# opencopcho.net
KiCad netlist of a schematic drawn in EAGLE
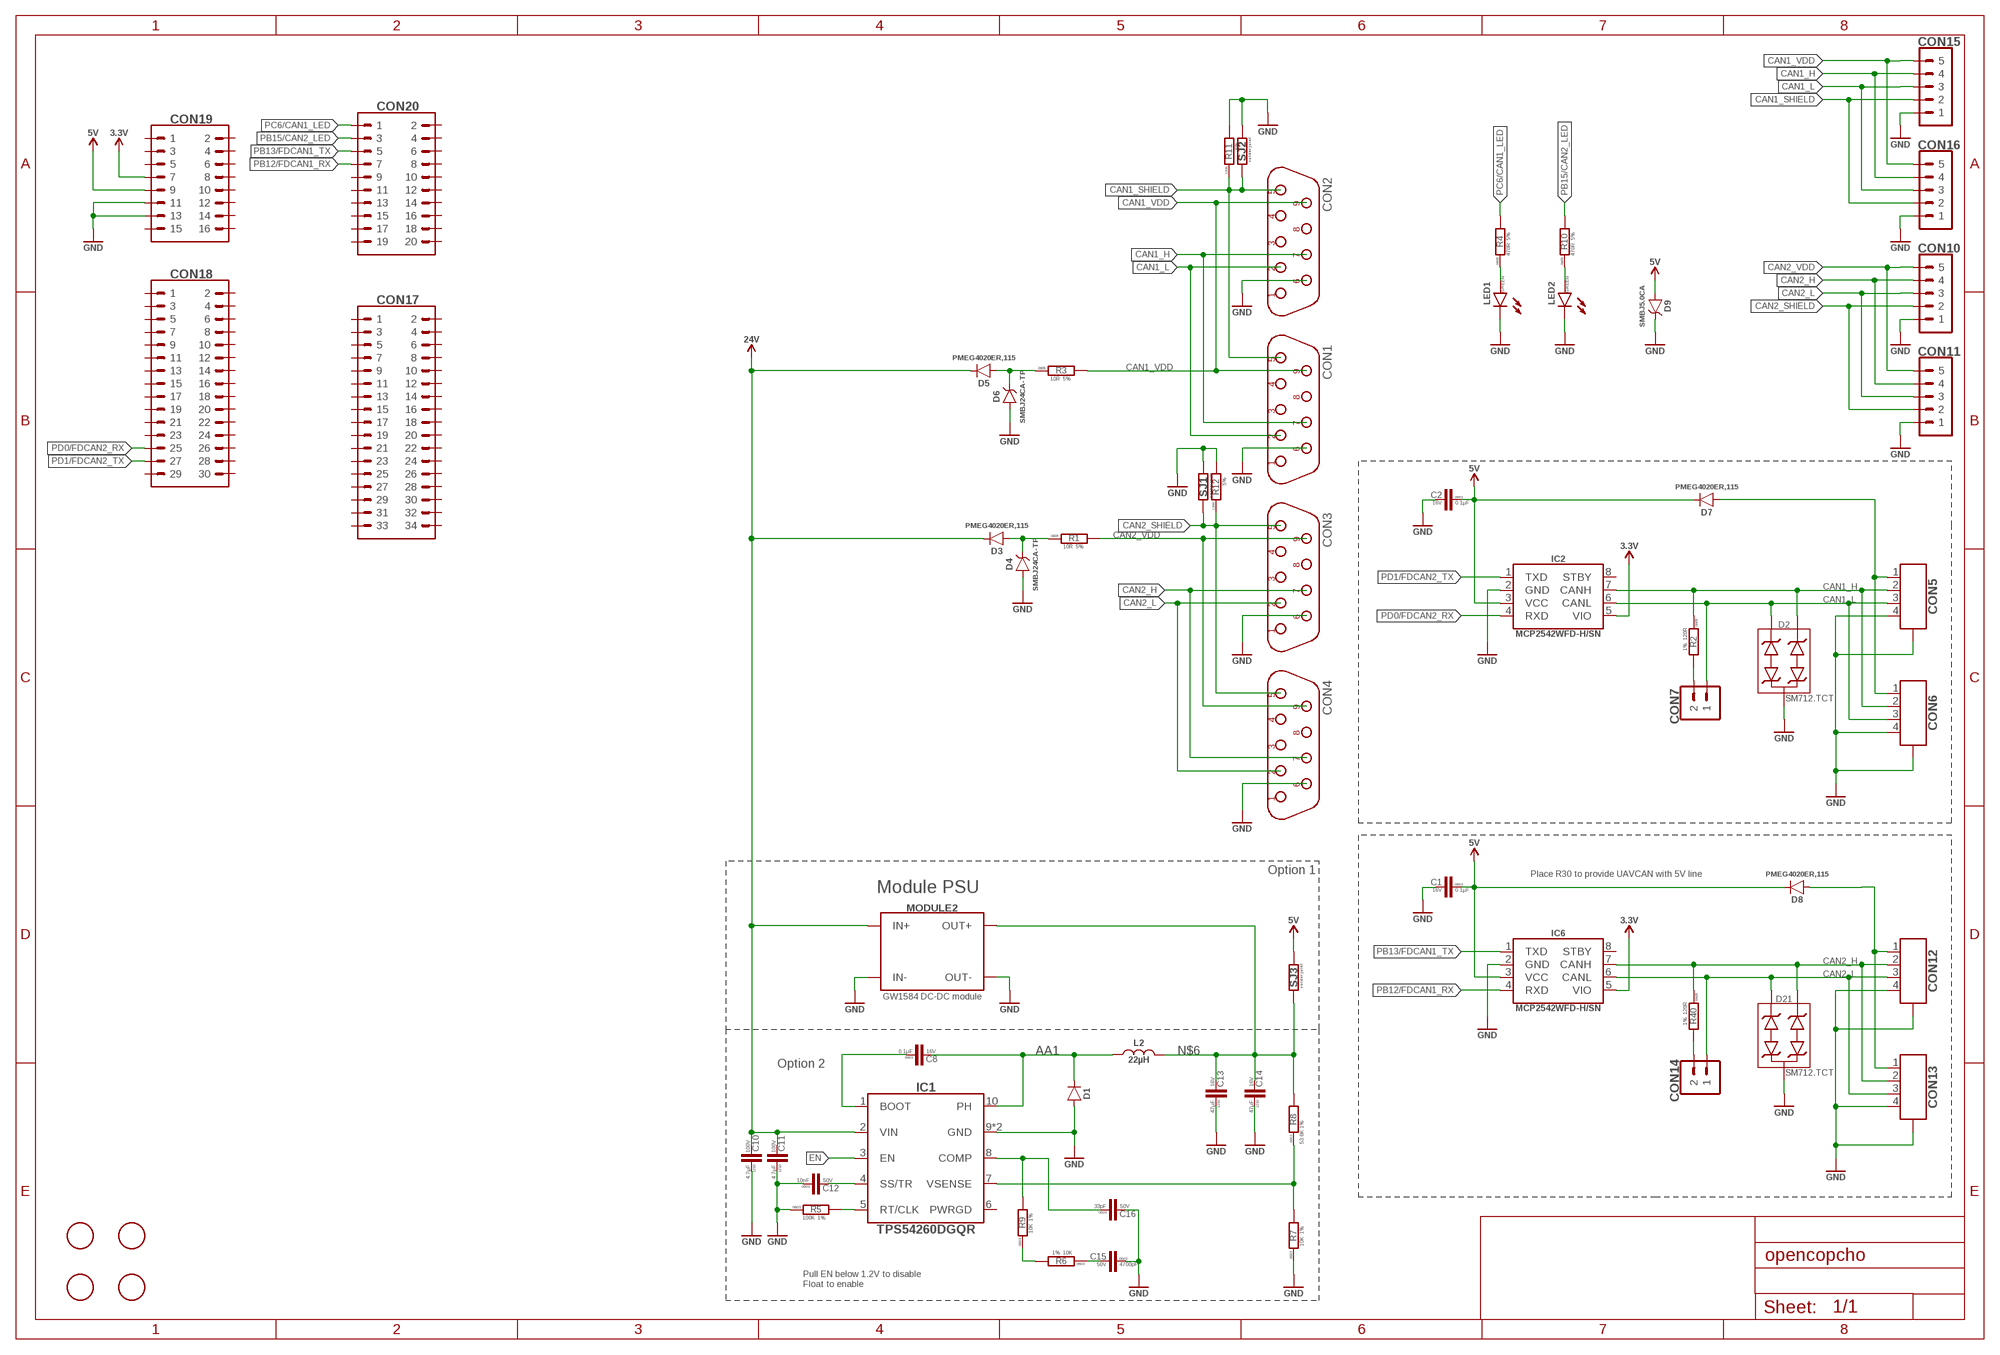
[diagram p0: schematic, sheet 1]

(export (version "E")
  (design (tool "Eeschema 10.0.6"))
  (components
    (comp (ref "C1")
      (value "0.1µF")
      (footprint "eagle-import:C0603")
      (fields
        (field (name "MANF") "Murata Electronics North America")
        (field (name "PACKAGE") "0603")
        (field (name "TOLERANCE") "+-10%")
        (field (name "VOLTAGE") "16V")
      )
      (libsource (lib "eagle-import") (part "0.1µF-0603-16V_10%_X7R"))
    )
    (comp (ref "C2")
      (value "0.1µF")
      (footprint "eagle-import:C0603")
      (fields
        (field (name "MANF") "Murata Electronics North America")
        (field (name "PACKAGE") "0603")
        (field (name "TOLERANCE") "+-10%")
        (field (name "VOLTAGE") "16V")
      )
      (libsource (lib "eagle-import") (part "0.1µF-0603-16V_10%_X7R"))
    )
    (comp (ref "C8")
      (value "0.1µF")
      (footprint "eagle-import:C0603")
      (fields
        (field (name "MANF") "Murata Electronics North America")
        (field (name "PACKAGE") "0603")
        (field (name "TOLERANCE") "+-10%")
        (field (name "VOLTAGE") "16V")
      )
      (libsource (lib "eagle-import") (part "0.1µF-0603-16V_10%_X7R"))
    )
    (comp (ref "C10")
      (value "4.7µF")
      (footprint "eagle-import:C1210")
      (fields
        (field (name "MANF") "TDK Corporation")
        (field (name "PACKAGE") "1210")
        (field (name "TOLERANCE") "+-20%")
        (field (name "VOLTAGE") "100V")
      )
      (libsource (lib "eagle-import") (part "4.7µF-1210-100V_20%_X7S"))
    )
    (comp (ref "C11")
      (value "4.7µF")
      (footprint "eagle-import:C1210")
      (fields
        (field (name "MANF") "TDK Corporation")
        (field (name "PACKAGE") "1210")
        (field (name "TOLERANCE") "+-20%")
        (field (name "VOLTAGE") "100V")
      )
      (libsource (lib "eagle-import") (part "4.7µF-1210-100V_20%_X7S"))
    )
    (comp (ref "C12")
      (value "10nF")
      (footprint "eagle-import:C0603")
      (fields
        (field (name "MANF") "YAGEO")
        (field (name "PACKAGE") "0603")
        (field (name "TOLERANCE") "+-10%")
        (field (name "VOLTAGE") "50V")
      )
      (libsource (lib "eagle-import") (part "10NF-0603-50V_10%_X7R"))
    )
    (comp (ref "C13")
      (value "47µF")
      (footprint "eagle-import:C1210")
      (fields
        (field (name "MANF") "Murata Electronics North America")
        (field (name "PACKAGE") "1210")
        (field (name "TOLERANCE") "+-20%")
        (field (name "VOLTAGE") "16V")
      )
      (libsource (lib "eagle-import") (part "47µF-1210-16V_20%_X5R"))
    )
    (comp (ref "C14")
      (value "47µF")
      (footprint "eagle-import:C1210")
      (fields
        (field (name "MANF") "Murata Electronics North America")
        (field (name "PACKAGE") "1210")
        (field (name "TOLERANCE") "+-20%")
        (field (name "VOLTAGE") "16V")
      )
      (libsource (lib "eagle-import") (part "47µF-1210-16V_20%_X5R"))
    )
    (comp (ref "C15")
      (value "4700pF")
      (footprint "eagle-import:C0603")
      (fields
        (field (name "MANF") "Murata Electronics North America")
        (field (name "PACKAGE") "0603")
        (field (name "TOLERANCE") "+-10%")
        (field (name "VOLTAGE") "50V")
      )
      (libsource (lib "eagle-import") (part "4700PF-0603-50V_10%_X7R"))
    )
    (comp (ref "C16")
      (value "33pF")
      (footprint "eagle-import:C0603")
      (fields
        (field (name "MANF") "Murata Electronics North America")
        (field (name "PACKAGE") "0603")
        (field (name "TOLERANCE") "+-5%")
        (field (name "VOLTAGE") "50V")
      )
      (libsource (lib "eagle-import") (part "33PF-0603-50V_5%_NP0"))
    )
    (comp (ref "CON1")
      (value "DB9-M")
      (footprint "eagle-import:D-09M")
      (fields (field (name "MANF") "Assmann WSW Components"))
      (libsource (lib "eagle-import") (part "DB9-M"))
    )
    (comp (ref "CON2")
      (value "DB9-M")
      (footprint "eagle-import:D-09M")
      (fields (field (name "MANF") "Assmann WSW Components"))
      (libsource (lib "eagle-import") (part "DB9-M"))
    )
    (comp (ref "CON3")
      (value "DB9-M")
      (footprint "eagle-import:D-09M")
      (fields (field (name "MANF") "Assmann WSW Components"))
      (libsource (lib "eagle-import") (part "DB9-M"))
    )
    (comp (ref "CON4")
      (value "DB9-M")
      (footprint "eagle-import:D-09M")
      (fields (field (name "MANF") "Assmann WSW Components"))
      (libsource (lib "eagle-import") (part "DB9-M"))
    )
    (comp (ref "CON5")
      (value "CON-4P-JST_GH-RA")
      (footprint "eagle-import:JST_GH-4P-RA")
      (fields (field (name "MANF") "JST Sales America Inc"))
      (libsource (lib "eagle-import") (part "CON-4P-RA-JST_GH"))
    )
    (comp (ref "CON6")
      (value "CON-4P-JST_GH-RA")
      (footprint "eagle-import:JST_GH-4P-RA")
      (fields (field (name "MANF") "JST Sales America Inc"))
      (libsource (lib "eagle-import") (part "CON-4P-RA-JST_GH"))
    )
    (comp (ref "CON7")
      (value "PINHEAD_1X02-2.54")
      (footprint "eagle-import:1X02-PTH-2.54")
      (libsource (lib "eagle-import") (part "PINHEAD_1X02-2.54"))
    )
    (comp (ref "CON10")
      (value "PINHEAD_1X05-2.54-KEY")
      (footprint "eagle-import:1X05-PTH-2.54-KEY")
      (fields (field (name "MANF") "Sullins Connector Solutions"))
      (libsource (lib "eagle-import") (part "PINHEAD_1X05-2.54-KEY"))
    )
    (comp (ref "CON11")
      (value "PINHEAD_1X05-2.54-KEY")
      (footprint "eagle-import:1X05-PTH-2.54-KEY")
      (fields (field (name "MANF") "Sullins Connector Solutions"))
      (libsource (lib "eagle-import") (part "PINHEAD_1X05-2.54-KEY"))
    )
    (comp (ref "CON12")
      (value "CON-4P-JST_GH-RA")
      (footprint "eagle-import:JST_GH-4P-RA")
      (fields (field (name "MANF") "JST Sales America Inc"))
      (libsource (lib "eagle-import") (part "CON-4P-RA-JST_GH"))
    )
    (comp (ref "CON13")
      (value "CON-4P-JST_GH-RA")
      (footprint "eagle-import:JST_GH-4P-RA")
      (fields (field (name "MANF") "JST Sales America Inc"))
      (libsource (lib "eagle-import") (part "CON-4P-RA-JST_GH"))
    )
    (comp (ref "CON14")
      (value "PINHEAD_1X02-2.54")
      (footprint "eagle-import:1X02-PTH-2.54")
      (libsource (lib "eagle-import") (part "PINHEAD_1X02-2.54"))
    )
    (comp (ref "CON15")
      (value "PINHEAD_1X05-2.54-KEY")
      (footprint "eagle-import:1X05-PTH-2.54-KEY")
      (fields (field (name "MANF") "Sullins Connector Solutions"))
      (libsource (lib "eagle-import") (part "PINHEAD_1X05-2.54-KEY"))
    )
    (comp (ref "CON16")
      (value "PINHEAD_1X05-2.54-KEY")
      (footprint "eagle-import:1X05-PTH-2.54-KEY")
      (fields (field (name "MANF") "Sullins Connector Solutions"))
      (libsource (lib "eagle-import") (part "PINHEAD_1X05-2.54-KEY"))
    )
    (comp (ref "CON17")
      (value "PINHEAD_2X17-TH-FEMALE-LONG")
      (footprint "eagle-import:2X17-PTH-2.54-FEMALE-LONG_PINS")
      (fields (field (name "MANF") "Samtec Inc"))
      (libsource (lib "eagle-import") (part "PINHEAD_2X17-TH-FEMALE-LONG"))
    )
    (comp (ref "CON18")
      (value "PINHEAD_2X15-2.54-FEMALE-LONG")
      (footprint "eagle-import:2X15-PTH-2.54-FEMALE-LONG-PINS")
      (libsource (lib "eagle-import") (part "PINHEAD_2X15-2.54-FEMALE-LONG"))
    )
    (comp (ref "CON19")
      (value "PINHEAD_2X08-TH-FEMALE-LONG")
      (footprint "eagle-import:2X08-PTH-2.54-FEMALE-LONG-PINS")
      (fields (field (name "MANF") "Samtec Inc"))
      (libsource (lib "eagle-import") (part "PINHEAD_2X08-TH-FEMALE-LONG"))
    )
    (comp (ref "CON20")
      (value "PINHEAD_2X10-2.54-TH-FEMALE-LONG")
      (footprint "eagle-import:2X10-PTH-2.54-FEMALE-LONG-PINS")
      (fields (field (name "MANF") "Samtec Inc"))
      (libsource (lib "eagle-import") (part "PINHEAD_2X10-2.54-TH-FEMALE-LONG"))
    )
    (comp (ref "D1")
      (value "B360B")
      (footprint "eagle-import:DO-214AA(SMB)")
      (fields
        (field (name "MANF") "Diodes Incorporated")
        (field (name "DIGIKEY#") "B360B-FDICT-ND")
        (field (name "MANF_1") "Diodes Incorporated")
        (field (name "MANF#") "B360B-13-F")
      )
      (libsource (lib "eagle-import") (part "B360B"))
    )
    (comp (ref "D2")
      (value "SM712")
      (footprint "eagle-import:SOT23B-3")
      (fields (field (name "MANF#") "SM712.TCT") (field (name "MANF") "Semtech Corporation"))
      (libsource (lib "eagle-import") (part "SM712"))
    )
    (comp (ref "D3")
      (value "PMEG4020")
      (footprint "eagle-import:SOD123W")
      (fields
        (field (name "MANF#") "PMEG4020ER,115")
        (field (name "MANF") "NXP Semiconductors")
        (field (name "VOLTAGE") "40V")
      )
      (libsource (lib "eagle-import") (part "PMEG4020"))
    )
    (comp (ref "D4")
      (value "SMBJ24CA-SMB")
      (footprint "eagle-import:DO-214AA(SMB)")
      (fields (field (name "MANF#") "SMBJ24CA-TP") (field (name "MANF") "Micro Commercial Co"))
      (libsource (lib "eagle-import") (part "SMBJ24CA-SMB"))
    )
    (comp (ref "D5")
      (value "PMEG4020")
      (footprint "eagle-import:SOD123W")
      (fields
        (field (name "MANF#") "PMEG4020ER,115")
        (field (name "MANF") "NXP Semiconductors")
        (field (name "VOLTAGE") "40V")
      )
      (libsource (lib "eagle-import") (part "PMEG4020"))
    )
    (comp (ref "D6")
      (value "SMBJ24CA-SMB")
      (footprint "eagle-import:DO-214AA(SMB)")
      (fields (field (name "MANF#") "SMBJ24CA-TP") (field (name "MANF") "Micro Commercial Co"))
      (libsource (lib "eagle-import") (part "SMBJ24CA-SMB"))
    )
    (comp (ref "D7")
      (value "PMEG4020")
      (footprint "eagle-import:SOD123W")
      (fields
        (field (name "MANF#") "PMEG4020ER,115")
        (field (name "MANF") "NXP Semiconductors")
        (field (name "VOLTAGE") "40V")
      )
      (libsource (lib "eagle-import") (part "PMEG4020"))
    )
    (comp (ref "D8")
      (value "PMEG4020")
      (footprint "eagle-import:SOD123W")
      (fields
        (field (name "MANF#") "PMEG4020ER,115")
        (field (name "MANF") "NXP Semiconductors")
        (field (name "VOLTAGE") "40V")
      )
      (libsource (lib "eagle-import") (part "PMEG4020"))
    )
    (comp (ref "D9")
      (value "SMBJ5.0CA-SMB")
      (footprint "eagle-import:DO-214AA(SMB)")
      (fields (field (name "MANF#") "SMBJ5.0CA") (field (name "MANF") "Bourns Inc"))
      (libsource (lib "eagle-import") (part "SMBJ5.0CA-SMB"))
    )
    (comp (ref "D21")
      (value "SM712")
      (footprint "eagle-import:SOT23B-3")
      (fields (field (name "MANF#") "SM712.TCT") (field (name "MANF") "Semtech Corporation"))
      (libsource (lib "eagle-import") (part "SM712"))
    )
    (comp (ref "IC1")
      (value "TPS54260")
      (footprint "eagle-import:MSOP10")
      (fields (field (name "MANF#") "TPS54260DGQR") (field (name "MANF") "Texas Instruments"))
      (libsource (lib "eagle-import") (part "TPS54260"))
    )
    (comp (ref "IC2")
      (value "MCP2542WFD")
      (footprint "eagle-import:SOIC8-3.9")
      (fields (field (name "MANF#") "MCP2542WFD-H/SN") (field (name "MANF") "Microchip Technology"))
      (libsource (lib "eagle-import") (part "MCP2542WFD"))
    )
    (comp (ref "IC6")
      (value "MCP2542WFD")
      (footprint "eagle-import:SOIC8-3.9")
      (fields (field (name "MANF#") "MCP2542WFD-H/SN") (field (name "MANF") "Microchip Technology"))
      (libsource (lib "eagle-import") (part "MCP2542WFD"))
    )
    (comp (ref "L2")
      (value "22µH")
      (footprint "eagle-import:SRP6540")
      (fields
        (field (name "MANF") "Bourns Inc")
        (field (name "DIGIKEY#") "SRP6540-4R7MCT-ND")
        (field (name "MANF_1") "Bourns Inc")
        (field (name "MANF#") "SRP6540-4R7M")
      )
      (libsource (lib "eagle-import") (part "22µH-SRP6540-22U"))
    )
    (comp (ref "LED1")
      (value "LED-0805")
      (footprint "eagle-import:LED0805")
      (fields (field (name "COLOR") "GREEN"))
      (libsource (lib "eagle-import") (part "LED-0805"))
    )
    (comp (ref "LED2")
      (value "LED-0805")
      (footprint "eagle-import:LED0805")
      (fields (field (name "COLOR") "GREEN"))
      (libsource (lib "eagle-import") (part "LED-0805"))
    )
    (comp (ref "MODULE2")
      (value "GW1584_MODULE")
      (footprint "eagle-import:GW1584_MODULE")
      (libsource (lib "eagle-import") (part "GW1584_MODULE"))
    )
    (comp (ref "R1")
      (value "10R")
      (footprint "eagle-import:R0805")
      (fields (field (name "PACKAGE") "0805") (field (name "TOLERANCE") "5%"))
      (libsource (lib "eagle-import") (part "R-0805-5%"))
    )
    (comp (ref "R2")
      (value "120R")
      (footprint "eagle-import:R0805")
      (fields (field (name "PACKAGE") "0805") (field (name "TOLERANCE") "1%"))
      (libsource (lib "eagle-import") (part "R-0805-1%"))
    )
    (comp (ref "R3")
      (value "10R")
      (footprint "eagle-import:R0805")
      (fields (field (name "PACKAGE") "0805") (field (name "TOLERANCE") "5%"))
      (libsource (lib "eagle-import") (part "R-0805-5%"))
    )
    (comp (ref "R4")
      (value "470R")
      (footprint "eagle-import:R0805")
      (fields (field (name "PACKAGE") "0805") (field (name "TOLERANCE") "5%"))
      (libsource (lib "eagle-import") (part "R-0805-5%"))
    )
    (comp (ref "R5")
      (value "100K")
      (footprint "eagle-import:R0603")
      (fields (field (name "MANF") "Yageo") (field (name "PACKAGE") "0603") (field (name "TOLERANCE") "1%"))
      (libsource (lib "eagle-import") (part "100K-0603-1%"))
    )
    (comp (ref "R6")
      (value "10K")
      (footprint "eagle-import:R0603")
      (fields (field (name "MANF") "Yageo") (field (name "PACKAGE") "0603") (field (name "TOLERANCE") "1%"))
      (libsource (lib "eagle-import") (part "10K-0603-1%"))
    )
    (comp (ref "R7")
      (value "10K")
      (footprint "eagle-import:R0603")
      (fields (field (name "MANF") "Yageo") (field (name "PACKAGE") "0603") (field (name "TOLERANCE") "1%"))
      (libsource (lib "eagle-import") (part "10K-0603-1%"))
    )
    (comp (ref "R8")
      (value "53.6K 1%")
      (footprint "eagle-import:R0603")
      (fields (field (name "PACKAGE") "0603") (field (name "TOLERANCE") "1%") (field (name "MANF") "Yageo"))
      (libsource (lib "eagle-import") (part "R-0603-1%"))
    )
    (comp (ref "R9")
      (value "10K")
      (footprint "eagle-import:R0603")
      (fields (field (name "MANF") "Yageo") (field (name "PACKAGE") "0603") (field (name "TOLERANCE") "1%"))
      (libsource (lib "eagle-import") (part "10K-0603-1%"))
    )
    (comp (ref "R10")
      (value "470R")
      (footprint "eagle-import:R0805")
      (fields (field (name "PACKAGE") "0805") (field (name "TOLERANCE") "5%"))
      (libsource (lib "eagle-import") (part "R-0805-5%"))
    )
    (comp (ref "R11")
      (value "R-5%-1206")
      (footprint "eagle-import:R1206")
      (fields (field (name "PACKAGE") "1206") (field (name "TOLERANCE") "5%"))
      (libsource (lib "eagle-import") (part "R-1206-5%"))
    )
    (comp (ref "R12")
      (value "R-5%-1206")
      (footprint "eagle-import:R1206")
      (fields (field (name "PACKAGE") "1206") (field (name "TOLERANCE") "5%"))
      (libsource (lib "eagle-import") (part "R-1206-5%"))
    )
    (comp (ref "R40")
      (value "120R")
      (footprint "eagle-import:R0805")
      (fields (field (name "PACKAGE") "0805") (field (name "TOLERANCE") "1%"))
      (libsource (lib "eagle-import") (part "R-0805-1%"))
    )
    (comp (ref "SJ1")
      (value "SOLDER_JOINT")
      (footprint "eagle-import:RES_0")
      (libsource (lib "eagle-import") (part "SOLDER_JOINT"))
    )
    (comp (ref "SJ2")
      (value "SOLDER_JOINT")
      (footprint "eagle-import:RES_0")
      (libsource (lib "eagle-import") (part "SOLDER_JOINT"))
    )
    (comp (ref "SJ3")
      (value "SOLDER_JOINT")
      (footprint "eagle-import:RES_0")
      (libsource (lib "eagle-import") (part "SOLDER_JOINT"))
    )
    (comp (ref "U$5")
      (value "FIDUCIALMOUNT")
      (footprint "eagle-import:FIDUCIA-MOUNT")
      (libsource (lib "eagle-import") (part "FIDUCIALMOUNT"))
    )
    (comp (ref "U$6")
      (value "FIDUCIALMOUNT")
      (footprint "eagle-import:FIDUCIA-MOUNT")
      (libsource (lib "eagle-import") (part "FIDUCIALMOUNT"))
    )
    (comp (ref "U$7")
      (value "FIDUCIALMOUNT")
      (footprint "eagle-import:FIDUCIA-MOUNT")
      (libsource (lib "eagle-import") (part "FIDUCIALMOUNT"))
    )
    (comp (ref "U$11")
      (value "FIDUCIALMOUNT")
      (footprint "eagle-import:FIDUCIA-MOUNT")
      (libsource (lib "eagle-import") (part "FIDUCIALMOUNT"))
    )
  )
  (nets
    (net (code "1") (name "/AA1") (class "Default")
      (node (ref "C8") (pin "P$2") (pinfunction "2_P$2") (pintype "passive"))
      (node (ref "D1") (pin "C") (pinfunction "C_C") (pintype "passive"))
      (node (ref "IC1") (pin "10") (pinfunction "PH_10") (pintype "bidirectional"))
      (node (ref "L2") (pin "1") (pinfunction "P$1_1") (pintype "bidirectional"))
    )
    (net (code "2") (name "/N$6") (class "Default")
      (node (ref "C13") (pin "2") (pinfunction "2_2") (pintype "passive"))
      (node (ref "C14") (pin "2") (pinfunction "2_2") (pintype "passive"))
      (node (ref "L2") (pin "2") (pinfunction "P$2_2") (pintype "bidirectional"))
      (node (ref "MODULE2") (pin "OUT+@1") (pinfunction "OUT+_OUT+@1") (pintype "bidirectional"))
      (node (ref "MODULE2") (pin "OUT+@2") (pinfunction "OUT+_OUT+@2") (pintype "bidirectional"))
      (node (ref "R8") (pin "2") (pinfunction "2_2") (pintype "passive"))
      (node (ref "SJ3") (pin "1") (pinfunction "1_1") (pintype "passive"))
    )
    (net (code "3") (name "3.3V") (class "Default")
      (node (ref "CON19") (pin "7") (pinfunction "7_7") (pintype "passive"))
      (node (ref "IC2") (pin "5") (pinfunction "VIO_5") (pintype "bidirectional"))
      (node (ref "IC6") (pin "5") (pinfunction "VIO_5") (pintype "bidirectional"))
    )
    (net (code "4") (name "5V") (class "Default")
      (node (ref "C1") (pin "P$1") (pinfunction "1_P$1") (pintype "passive"))
      (node (ref "C2") (pin "P$1") (pinfunction "1_P$1") (pintype "passive"))
      (node (ref "CON19") (pin "9") (pinfunction "9_9") (pintype "passive"))
      (node (ref "D7") (pin "C") (pinfunction "C_C") (pintype "passive"))
      (node (ref "D8") (pin "C") (pinfunction "C_C") (pintype "passive"))
      (node (ref "D9") (pin "A") (pinfunction "A_A") (pintype "bidirectional"))
      (node (ref "IC2") (pin "3") (pinfunction "VCC_3") (pintype "bidirectional"))
      (node (ref "IC6") (pin "3") (pinfunction "VCC_3") (pintype "bidirectional"))
      (node (ref "SJ3") (pin "2") (pinfunction "2_2") (pintype "passive"))
    )
    (net (code "5") (name "24V") (class "Default")
      (node (ref "C10") (pin "2") (pinfunction "2_2") (pintype "passive"))
      (node (ref "C11") (pin "2") (pinfunction "2_2") (pintype "passive"))
      (node (ref "D3") (pin "C") (pinfunction "C_C") (pintype "passive"))
      (node (ref "D5") (pin "C") (pinfunction "C_C") (pintype "passive"))
      (node (ref "IC1") (pin "2") (pinfunction "VIN_2") (pintype "bidirectional"))
      (node (ref "MODULE2") (pin "IN+@1") (pinfunction "IN+_IN+@1") (pintype "bidirectional"))
      (node (ref "MODULE2") (pin "IN+@2") (pinfunction "IN+_IN+@2") (pintype "bidirectional"))
    )
    (net (code "6") (name "CAN1_H") (class "Default")
      (node (ref "CON1") (pin "7") (pinfunction "7_7") (pintype "passive"))
      (node (ref "CON15") (pin "4") (pinfunction "4_4") (pintype "passive"))
      (node (ref "CON16") (pin "4") (pinfunction "4_4") (pintype "passive"))
      (node (ref "CON2") (pin "7") (pinfunction "7_7") (pintype "passive"))
      (node (ref "CON5") (pin "2") (pinfunction "2_2") (pintype "bidirectional"))
      (node (ref "CON6") (pin "2") (pinfunction "2_2") (pintype "bidirectional"))
      (node (ref "D2") (pin "1") (pinfunction "C3_1") (pintype "bidirectional"))
      (node (ref "IC2") (pin "7") (pinfunction "CANH_7") (pintype "bidirectional"))
      (node (ref "R2") (pin "1") (pinfunction "1_1") (pintype "passive"))
    )
    (net (code "7") (name "CAN1_L") (class "Default")
      (node (ref "CON1") (pin "2") (pinfunction "2_2") (pintype "passive"))
      (node (ref "CON15") (pin "3") (pinfunction "3_3") (pintype "passive"))
      (node (ref "CON16") (pin "3") (pinfunction "3_3") (pintype "passive"))
      (node (ref "CON2") (pin "2") (pinfunction "2_2") (pintype "passive"))
      (node (ref "CON5") (pin "3") (pinfunction "3_3") (pintype "bidirectional"))
      (node (ref "CON6") (pin "3") (pinfunction "3_3") (pintype "bidirectional"))
      (node (ref "CON7") (pin "1") (pinfunction "1_1") (pintype "passive"))
      (node (ref "D2") (pin "2") (pinfunction "C2_2") (pintype "bidirectional"))
      (node (ref "IC2") (pin "6") (pinfunction "CANL_6") (pintype "bidirectional"))
    )
    (net (code "8") (name "CAN1_SHIELD") (class "Default")
      (node (ref "CON1") (pin "5") (pinfunction "5_5") (pintype "passive"))
      (node (ref "CON15") (pin "2") (pinfunction "2_2") (pintype "passive"))
      (node (ref "CON16") (pin "2") (pinfunction "2_2") (pintype "passive"))
      (node (ref "CON2") (pin "5") (pinfunction "5_5") (pintype "passive"))
      (node (ref "R11") (pin "P$1") (pinfunction "1_P$1") (pintype "passive"))
      (node (ref "SJ2") (pin "1") (pinfunction "1_1") (pintype "passive"))
    )
    (net (code "9") (name "CAN1_VDD") (class "Default")
      (node (ref "CON1") (pin "9") (pinfunction "9_9") (pintype "passive"))
      (node (ref "CON15") (pin "5") (pinfunction "5_5") (pintype "passive"))
      (node (ref "CON16") (pin "5") (pinfunction "5_5") (pintype "passive"))
      (node (ref "CON2") (pin "9") (pinfunction "9_9") (pintype "passive"))
      (node (ref "R3") (pin "2") (pinfunction "2_2") (pintype "passive"))
    )
    (net (code "10") (name "CAN2_H") (class "Default")
      (node (ref "CON10") (pin "4") (pinfunction "4_4") (pintype "passive"))
      (node (ref "CON11") (pin "4") (pinfunction "4_4") (pintype "passive"))
      (node (ref "CON12") (pin "2") (pinfunction "2_2") (pintype "bidirectional"))
      (node (ref "CON13") (pin "2") (pinfunction "2_2") (pintype "bidirectional"))
      (node (ref "CON3") (pin "7") (pinfunction "7_7") (pintype "passive"))
      (node (ref "CON4") (pin "7") (pinfunction "7_7") (pintype "passive"))
      (node (ref "D21") (pin "1") (pinfunction "C3_1") (pintype "bidirectional"))
      (node (ref "IC6") (pin "7") (pinfunction "CANH_7") (pintype "bidirectional"))
      (node (ref "R40") (pin "1") (pinfunction "1_1") (pintype "passive"))
    )
    (net (code "11") (name "CAN2_L") (class "Default")
      (node (ref "CON10") (pin "3") (pinfunction "3_3") (pintype "passive"))
      (node (ref "CON11") (pin "3") (pinfunction "3_3") (pintype "passive"))
      (node (ref "CON12") (pin "3") (pinfunction "3_3") (pintype "bidirectional"))
      (node (ref "CON13") (pin "3") (pinfunction "3_3") (pintype "bidirectional"))
      (node (ref "CON14") (pin "1") (pinfunction "1_1") (pintype "passive"))
      (node (ref "CON3") (pin "2") (pinfunction "2_2") (pintype "passive"))
      (node (ref "CON4") (pin "2") (pinfunction "2_2") (pintype "passive"))
      (node (ref "D21") (pin "2") (pinfunction "C2_2") (pintype "bidirectional"))
      (node (ref "IC6") (pin "6") (pinfunction "CANL_6") (pintype "bidirectional"))
    )
    (net (code "12") (name "CAN2_SHIELD") (class "Default")
      (node (ref "CON10") (pin "2") (pinfunction "2_2") (pintype "passive"))
      (node (ref "CON11") (pin "2") (pinfunction "2_2") (pintype "passive"))
      (node (ref "CON3") (pin "5") (pinfunction "5_5") (pintype "passive"))
      (node (ref "CON4") (pin "5") (pinfunction "5_5") (pintype "passive"))
      (node (ref "R12") (pin "P$1") (pinfunction "1_P$1") (pintype "passive"))
      (node (ref "SJ1") (pin "1") (pinfunction "1_1") (pintype "passive"))
    )
    (net (code "13") (name "CAN2_VDD") (class "Default")
      (node (ref "CON10") (pin "5") (pinfunction "5_5") (pintype "passive"))
      (node (ref "CON11") (pin "5") (pinfunction "5_5") (pintype "passive"))
      (node (ref "CON3") (pin "9") (pinfunction "9_9") (pintype "passive"))
      (node (ref "CON4") (pin "9") (pinfunction "9_9") (pintype "passive"))
      (node (ref "R1") (pin "2") (pinfunction "2_2") (pintype "passive"))
    )
    (net (code "14") (name "EN") (class "Default")
      (node (ref "IC1") (pin "3") (pinfunction "EN_3") (pintype "bidirectional"))
    )
    (net (code "15") (name "GND") (class "Default")
      (node (ref "C1") (pin "P$2") (pinfunction "2_P$2") (pintype "passive"))
      (node (ref "C10") (pin "1") (pinfunction "1_1") (pintype "passive"))
      (node (ref "C11") (pin "1") (pinfunction "1_1") (pintype "passive"))
      (node (ref "C12") (pin "P$1") (pinfunction "1_P$1") (pintype "passive"))
      (node (ref "C13") (pin "1") (pinfunction "1_1") (pintype "passive"))
      (node (ref "C14") (pin "1") (pinfunction "1_1") (pintype "passive"))
      (node (ref "C15") (pin "P$1") (pinfunction "1_P$1") (pintype "passive"))
      (node (ref "C16") (pin "P$2") (pinfunction "2_P$2") (pintype "passive"))
      (node (ref "C2") (pin "P$2") (pinfunction "2_P$2") (pintype "passive"))
      (node (ref "CON1") (pin "6") (pinfunction "6_6") (pintype "passive"))
      (node (ref "CON10") (pin "1") (pinfunction "1_1") (pintype "passive"))
      (node (ref "CON11") (pin "1") (pinfunction "1_1") (pintype "passive"))
      (node (ref "CON12") (pin "4") (pinfunction "4_4") (pintype "bidirectional"))
      (node (ref "CON12") (pin "M$0") (pinfunction "GND_M$0") (pintype "bidirectional"))
      (node (ref "CON12") (pin "M$1") (pinfunction "GND_M$1") (pintype "bidirectional"))
      (node (ref "CON13") (pin "4") (pinfunction "4_4") (pintype "bidirectional"))
      (node (ref "CON13") (pin "M$0") (pinfunction "GND_M$0") (pintype "bidirectional"))
      (node (ref "CON13") (pin "M$1") (pinfunction "GND_M$1") (pintype "bidirectional"))
      (node (ref "CON15") (pin "1") (pinfunction "1_1") (pintype "passive"))
      (node (ref "CON16") (pin "1") (pinfunction "1_1") (pintype "passive"))
      (node (ref "CON19") (pin "11") (pinfunction "11_11") (pintype "passive"))
      (node (ref "CON19") (pin "13") (pinfunction "13_13") (pintype "passive"))
      (node (ref "CON2") (pin "6") (pinfunction "6_6") (pintype "passive"))
      (node (ref "CON3") (pin "6") (pinfunction "6_6") (pintype "passive"))
      (node (ref "CON4") (pin "6") (pinfunction "6_6") (pintype "passive"))
      (node (ref "CON5") (pin "4") (pinfunction "4_4") (pintype "bidirectional"))
      (node (ref "CON5") (pin "M$0") (pinfunction "GND_M$0") (pintype "bidirectional"))
      (node (ref "CON5") (pin "M$1") (pinfunction "GND_M$1") (pintype "bidirectional"))
      (node (ref "CON6") (pin "4") (pinfunction "4_4") (pintype "bidirectional"))
      (node (ref "CON6") (pin "M$0") (pinfunction "GND_M$0") (pintype "bidirectional"))
      (node (ref "CON6") (pin "M$1") (pinfunction "GND_M$1") (pintype "bidirectional"))
      (node (ref "D1") (pin "A") (pinfunction "A_A") (pintype "passive"))
      (node (ref "D2") (pin "3") (pinfunction "P$1_3") (pintype "bidirectional"))
      (node (ref "D21") (pin "3") (pinfunction "P$1_3") (pintype "bidirectional"))
      (node (ref "D4") (pin "A") (pinfunction "A_A") (pintype "bidirectional"))
      (node (ref "D6") (pin "A") (pinfunction "A_A") (pintype "bidirectional"))
      (node (ref "D9") (pin "C") (pinfunction "C_C") (pintype "bidirectional"))
      (node (ref "IC1") (pin "9") (pinfunction "GND_9") (pintype "bidirectional"))
      (node (ref "IC1") (pin "TPAD") (pinfunction "GND_TPAD") (pintype "bidirectional"))
      (node (ref "IC2") (pin "2") (pinfunction "GND_2") (pintype "bidirectional"))
      (node (ref "IC6") (pin "2") (pinfunction "GND_2") (pintype "bidirectional"))
      (node (ref "LED1") (pin "C") (pinfunction "C_C") (pintype "bidirectional"))
      (node (ref "LED2") (pin "C") (pinfunction "C_C") (pintype "bidirectional"))
      (node (ref "MODULE2") (pin "IN-@1") (pinfunction "IN-_IN-@1") (pintype "bidirectional"))
      (node (ref "MODULE2") (pin "IN-@2") (pinfunction "IN-_IN-@2") (pintype "bidirectional"))
      (node (ref "MODULE2") (pin "OUT-@1") (pinfunction "OUT-_OUT-@1") (pintype "bidirectional"))
      (node (ref "MODULE2") (pin "OUT-@2") (pinfunction "OUT-_OUT-@2") (pintype "bidirectional"))
      (node (ref "R11") (pin "P$2") (pinfunction "2_P$2") (pintype "passive"))
      (node (ref "R12") (pin "P$2") (pinfunction "2_P$2") (pintype "passive"))
      (node (ref "R5") (pin "P$1") (pinfunction "1_P$1") (pintype "passive"))
      (node (ref "R7") (pin "P$1") (pinfunction "1_P$1") (pintype "passive"))
      (node (ref "SJ1") (pin "2") (pinfunction "2_2") (pintype "passive"))
      (node (ref "SJ2") (pin "2") (pinfunction "2_2") (pintype "passive"))
    )
    (net (code "16") (name "Net-(C8-1)") (class "Default")
      (node (ref "C8") (pin "P$1") (pinfunction "1_P$1") (pintype "passive"))
      (node (ref "IC1") (pin "1") (pinfunction "BOOT_1") (pintype "bidirectional"))
    )
    (net (code "17") (name "Net-(C12-2)") (class "Default")
      (node (ref "C12") (pin "P$2") (pinfunction "2_P$2") (pintype "passive"))
      (node (ref "IC1") (pin "4") (pinfunction "SS/TR_4") (pintype "bidirectional"))
    )
    (net (code "18") (name "Net-(C15-2)") (class "Default")
      (node (ref "C15") (pin "P$2") (pinfunction "2_P$2") (pintype "passive"))
      (node (ref "R6") (pin "P$1") (pinfunction "1_P$1") (pintype "passive"))
    )
    (net (code "19") (name "Net-(C16-1)") (class "Default")
      (node (ref "C16") (pin "P$1") (pinfunction "1_P$1") (pintype "passive"))
      (node (ref "IC1") (pin "8") (pinfunction "COMP_8") (pintype "bidirectional"))
      (node (ref "R9") (pin "P$2") (pinfunction "2_P$2") (pintype "passive"))
    )
    (net (code "20") (name "Net-(CON5-Pad1)") (class "Default")
      (node (ref "CON5") (pin "1") (pinfunction "1_1") (pintype "bidirectional"))
      (node (ref "CON6") (pin "1") (pinfunction "1_1") (pintype "bidirectional"))
      (node (ref "D7") (pin "A") (pinfunction "A_A") (pintype "passive"))
    )
    (net (code "21") (name "Net-(CON7-Pad2)") (class "Default")
      (node (ref "CON7") (pin "2") (pinfunction "2_2") (pintype "passive"))
      (node (ref "R2") (pin "2") (pinfunction "2_2") (pintype "passive"))
    )
    (net (code "22") (name "Net-(CON12-Pad1)") (class "Default")
      (node (ref "CON12") (pin "1") (pinfunction "1_1") (pintype "bidirectional"))
      (node (ref "CON13") (pin "1") (pinfunction "1_1") (pintype "bidirectional"))
      (node (ref "D8") (pin "A") (pinfunction "A_A") (pintype "passive"))
    )
    (net (code "23") (name "Net-(CON14-Pad2)") (class "Default")
      (node (ref "CON14") (pin "2") (pinfunction "2_2") (pintype "passive"))
      (node (ref "R40") (pin "2") (pinfunction "2_2") (pintype "passive"))
    )
    (net (code "24") (name "Net-(D3-PadA)") (class "Default")
      (node (ref "D3") (pin "A") (pinfunction "A_A") (pintype "passive"))
      (node (ref "D4") (pin "C") (pinfunction "C_C") (pintype "bidirectional"))
      (node (ref "R1") (pin "1") (pinfunction "1_1") (pintype "passive"))
    )
    (net (code "25") (name "Net-(D5-PadA)") (class "Default")
      (node (ref "D5") (pin "A") (pinfunction "A_A") (pintype "passive"))
      (node (ref "D6") (pin "C") (pinfunction "C_C") (pintype "bidirectional"))
      (node (ref "R3") (pin "1") (pinfunction "1_1") (pintype "passive"))
    )
    (net (code "26") (name "Net-(IC1-RT{slash}CLK)") (class "Default")
      (node (ref "IC1") (pin "5") (pinfunction "RT/CLK_5") (pintype "bidirectional"))
      (node (ref "R5") (pin "P$2") (pinfunction "2_P$2") (pintype "passive"))
    )
    (net (code "27") (name "Net-(IC1-VSENSE)") (class "Default")
      (node (ref "IC1") (pin "7") (pinfunction "VSENSE_7") (pintype "bidirectional"))
      (node (ref "R7") (pin "P$2") (pinfunction "2_P$2") (pintype "passive"))
      (node (ref "R8") (pin "1") (pinfunction "1_1") (pintype "passive"))
    )
    (net (code "28") (name "Net-(LED1-PadA)") (class "Default")
      (node (ref "LED1") (pin "A") (pinfunction "A_A") (pintype "bidirectional"))
      (node (ref "R4") (pin "1") (pinfunction "1_1") (pintype "passive"))
    )
    (net (code "29") (name "Net-(LED2-PadA)") (class "Default")
      (node (ref "LED2") (pin "A") (pinfunction "A_A") (pintype "bidirectional"))
      (node (ref "R10") (pin "1") (pinfunction "1_1") (pintype "passive"))
    )
    (net (code "30") (name "Net-(R6-2)") (class "Default")
      (node (ref "R6") (pin "P$2") (pinfunction "2_P$2") (pintype "passive"))
      (node (ref "R9") (pin "P$1") (pinfunction "1_P$1") (pintype "passive"))
    )
    (net (code "31") (name "PB12{slash}FDCAN1_RX") (class "Default")
      (node (ref "CON20") (pin "7") (pinfunction "7_7") (pintype "passive"))
      (node (ref "IC6") (pin "4") (pinfunction "RXD_4") (pintype "bidirectional"))
    )
    (net (code "32") (name "PB13{slash}FDCAN1_TX") (class "Default")
      (node (ref "CON20") (pin "5") (pinfunction "5_5") (pintype "passive"))
      (node (ref "IC6") (pin "1") (pinfunction "TXD_1") (pintype "bidirectional"))
    )
    (net (code "33") (name "PB15{slash}CAN2_LED") (class "Default")
      (node (ref "CON20") (pin "3") (pinfunction "3_3") (pintype "passive"))
      (node (ref "R10") (pin "2") (pinfunction "2_2") (pintype "passive"))
    )
    (net (code "34") (name "PC6{slash}CAN1_LED") (class "Default")
      (node (ref "CON20") (pin "1") (pinfunction "1_1") (pintype "passive"))
      (node (ref "R4") (pin "2") (pinfunction "2_2") (pintype "passive"))
    )
    (net (code "35") (name "PD0{slash}FDCAN2_RX") (class "Default")
      (node (ref "CON18") (pin "25") (pinfunction "25_25") (pintype "passive"))
      (node (ref "IC2") (pin "4") (pinfunction "RXD_4") (pintype "bidirectional"))
    )
    (net (code "36") (name "PD1{slash}FDCAN2_TX") (class "Default")
      (node (ref "CON18") (pin "27") (pinfunction "27_27") (pintype "passive"))
      (node (ref "IC2") (pin "1") (pinfunction "TXD_1") (pintype "bidirectional"))
    )
    (net (code "37") (name "unconnected-(CON1-Pad1)") (class "Default")
      (node (ref "CON1") (pin "1") (pinfunction "1_1") (pintype "passive"))
    )
    (net (code "38") (name "unconnected-(CON1-Pad3)") (class "Default")
      (node (ref "CON1") (pin "3") (pinfunction "3_3") (pintype "passive"))
    )
    (net (code "39") (name "unconnected-(CON1-Pad4)") (class "Default")
      (node (ref "CON1") (pin "4") (pinfunction "4_4") (pintype "passive"))
    )
    (net (code "40") (name "unconnected-(CON1-Pad8)") (class "Default")
      (node (ref "CON1") (pin "8") (pinfunction "8_8") (pintype "passive"))
    )
    (net (code "41") (name "unconnected-(CON2-Pad1)") (class "Default")
      (node (ref "CON2") (pin "1") (pinfunction "1_1") (pintype "passive"))
    )
    (net (code "42") (name "unconnected-(CON2-Pad3)") (class "Default")
      (node (ref "CON2") (pin "3") (pinfunction "3_3") (pintype "passive"))
    )
    (net (code "43") (name "unconnected-(CON2-Pad4)") (class "Default")
      (node (ref "CON2") (pin "4") (pinfunction "4_4") (pintype "passive"))
    )
    (net (code "44") (name "unconnected-(CON2-Pad8)") (class "Default")
      (node (ref "CON2") (pin "8") (pinfunction "8_8") (pintype "passive"))
    )
    (net (code "45") (name "unconnected-(CON3-Pad1)") (class "Default")
      (node (ref "CON3") (pin "1") (pinfunction "1_1") (pintype "passive"))
    )
    (net (code "46") (name "unconnected-(CON3-Pad3)") (class "Default")
      (node (ref "CON3") (pin "3") (pinfunction "3_3") (pintype "passive"))
    )
    (net (code "47") (name "unconnected-(CON3-Pad4)") (class "Default")
      (node (ref "CON3") (pin "4") (pinfunction "4_4") (pintype "passive"))
    )
    (net (code "48") (name "unconnected-(CON3-Pad8)") (class "Default")
      (node (ref "CON3") (pin "8") (pinfunction "8_8") (pintype "passive"))
    )
    (net (code "49") (name "unconnected-(CON4-Pad1)") (class "Default")
      (node (ref "CON4") (pin "1") (pinfunction "1_1") (pintype "passive"))
    )
    (net (code "50") (name "unconnected-(CON4-Pad3)") (class "Default")
      (node (ref "CON4") (pin "3") (pinfunction "3_3") (pintype "passive"))
    )
    (net (code "51") (name "unconnected-(CON4-Pad4)") (class "Default")
      (node (ref "CON4") (pin "4") (pinfunction "4_4") (pintype "passive"))
    )
    (net (code "52") (name "unconnected-(CON4-Pad8)") (class "Default")
      (node (ref "CON4") (pin "8") (pinfunction "8_8") (pintype "passive"))
    )
    (net (code "53") (name "unconnected-(CON17-Pad1)") (class "Default")
      (node (ref "CON17") (pin "1") (pinfunction "1_1") (pintype "passive"))
    )
    (net (code "54") (name "unconnected-(CON17-Pad2)") (class "Default")
      (node (ref "CON17") (pin "2") (pinfunction "2_2") (pintype "passive"))
    )
    (net (code "55") (name "unconnected-(CON17-Pad3)") (class "Default")
      (node (ref "CON17") (pin "3") (pinfunction "3_3") (pintype "passive"))
    )
    (net (code "56") (name "unconnected-(CON17-Pad4)") (class "Default")
      (node (ref "CON17") (pin "4") (pinfunction "4_4") (pintype "passive"))
    )
    (net (code "57") (name "unconnected-(CON17-Pad5)") (class "Default")
      (node (ref "CON17") (pin "5") (pinfunction "5_5") (pintype "passive"))
    )
    (net (code "58") (name "unconnected-(CON17-Pad6)") (class "Default")
      (node (ref "CON17") (pin "6") (pinfunction "6_6") (pintype "passive"))
    )
    (net (code "59") (name "unconnected-(CON17-Pad7)") (class "Default")
      (node (ref "CON17") (pin "7") (pinfunction "7_7") (pintype "passive"))
    )
    (net (code "60") (name "unconnected-(CON17-Pad8)") (class "Default")
      (node (ref "CON17") (pin "8") (pinfunction "8_8") (pintype "passive"))
    )
    (net (code "61") (name "unconnected-(CON17-Pad9)") (class "Default")
      (node (ref "CON17") (pin "9") (pinfunction "9_9") (pintype "passive"))
    )
    (net (code "62") (name "unconnected-(CON17-Pad10)") (class "Default")
      (node (ref "CON17") (pin "10") (pinfunction "10_10") (pintype "passive"))
    )
    (net (code "63") (name "unconnected-(CON17-Pad11)") (class "Default")
      (node (ref "CON17") (pin "11") (pinfunction "11_11") (pintype "passive"))
    )
    (net (code "64") (name "unconnected-(CON17-Pad12)") (class "Default")
      (node (ref "CON17") (pin "12") (pinfunction "12_12") (pintype "passive"))
    )
    (net (code "65") (name "unconnected-(CON17-Pad13)") (class "Default")
      (node (ref "CON17") (pin "13") (pinfunction "13_13") (pintype "passive"))
    )
    (net (code "66") (name "unconnected-(CON17-Pad14)") (class "Default")
      (node (ref "CON17") (pin "14") (pinfunction "14_14") (pintype "passive"))
    )
    (net (code "67") (name "unconnected-(CON17-Pad15)") (class "Default")
      (node (ref "CON17") (pin "15") (pinfunction "15_15") (pintype "passive"))
    )
    (net (code "68") (name "unconnected-(CON17-Pad16)") (class "Default")
      (node (ref "CON17") (pin "16") (pinfunction "16_16") (pintype "passive"))
    )
    (net (code "69") (name "unconnected-(CON17-Pad17)") (class "Default")
      (node (ref "CON17") (pin "17") (pinfunction "17_17") (pintype "passive"))
    )
    (net (code "70") (name "unconnected-(CON17-Pad18)") (class "Default")
      (node (ref "CON17") (pin "18") (pinfunction "18_18") (pintype "passive"))
    )
    (net (code "71") (name "unconnected-(CON17-Pad19)") (class "Default")
      (node (ref "CON17") (pin "19") (pinfunction "19_19") (pintype "passive"))
    )
    (net (code "72") (name "unconnected-(CON17-Pad20)") (class "Default")
      (node (ref "CON17") (pin "20") (pinfunction "20_20") (pintype "passive"))
    )
    (net (code "73") (name "unconnected-(CON17-Pad21)") (class "Default")
      (node (ref "CON17") (pin "21") (pinfunction "21_21") (pintype "passive"))
    )
    (net (code "74") (name "unconnected-(CON17-Pad22)") (class "Default")
      (node (ref "CON17") (pin "22") (pinfunction "22_22") (pintype "passive"))
    )
    (net (code "75") (name "unconnected-(CON17-Pad23)") (class "Default")
      (node (ref "CON17") (pin "23") (pinfunction "23_23") (pintype "passive"))
    )
    (net (code "76") (name "unconnected-(CON17-Pad24)") (class "Default")
      (node (ref "CON17") (pin "24") (pinfunction "24_24") (pintype "passive"))
    )
    (net (code "77") (name "unconnected-(CON17-Pad25)") (class "Default")
      (node (ref "CON17") (pin "25") (pinfunction "25_25") (pintype "passive"))
    )
    (net (code "78") (name "unconnected-(CON17-Pad26)") (class "Default")
      (node (ref "CON17") (pin "26") (pinfunction "26_26") (pintype "passive"))
    )
    (net (code "79") (name "unconnected-(CON17-Pad27)") (class "Default")
      (node (ref "CON17") (pin "27") (pinfunction "27_27") (pintype "passive"))
    )
    (net (code "80") (name "unconnected-(CON17-Pad28)") (class "Default")
      (node (ref "CON17") (pin "28") (pinfunction "28_28") (pintype "passive"))
    )
    (net (code "81") (name "unconnected-(CON17-Pad29)") (class "Default")
      (node (ref "CON17") (pin "29") (pinfunction "29_29") (pintype "passive"))
    )
    (net (code "82") (name "unconnected-(CON17-Pad30)") (class "Default")
      (node (ref "CON17") (pin "30") (pinfunction "30_30") (pintype "passive"))
    )
    (net (code "83") (name "unconnected-(CON17-Pad31)") (class "Default")
      (node (ref "CON17") (pin "31") (pinfunction "31_31") (pintype "passive"))
    )
    (net (code "84") (name "unconnected-(CON17-Pad32)") (class "Default")
      (node (ref "CON17") (pin "32") (pinfunction "32_32") (pintype "passive"))
    )
    (net (code "85") (name "unconnected-(CON17-Pad33)") (class "Default")
      (node (ref "CON17") (pin "33") (pinfunction "33_33") (pintype "passive"))
    )
    (net (code "86") (name "unconnected-(CON17-Pad34)") (class "Default")
      (node (ref "CON17") (pin "34") (pinfunction "34_34") (pintype "passive"))
    )
    (net (code "87") (name "unconnected-(CON18-Pad1)") (class "Default")
      (node (ref "CON18") (pin "1") (pinfunction "1_1") (pintype "passive"))
    )
    (net (code "88") (name "unconnected-(CON18-Pad2)") (class "Default")
      (node (ref "CON18") (pin "2") (pinfunction "2_2") (pintype "passive"))
    )
    (net (code "89") (name "unconnected-(CON18-Pad3)") (class "Default")
      (node (ref "CON18") (pin "3") (pinfunction "3_3") (pintype "passive"))
    )
    (net (code "90") (name "unconnected-(CON18-Pad4)") (class "Default")
      (node (ref "CON18") (pin "4") (pinfunction "4_4") (pintype "passive"))
    )
    (net (code "91") (name "unconnected-(CON18-Pad5)") (class "Default")
      (node (ref "CON18") (pin "5") (pinfunction "5_5") (pintype "passive"))
    )
    (net (code "92") (name "unconnected-(CON18-Pad6)") (class "Default")
      (node (ref "CON18") (pin "6") (pinfunction "6_6") (pintype "passive"))
    )
    (net (code "93") (name "unconnected-(CON18-Pad7)") (class "Default")
      (node (ref "CON18") (pin "7") (pinfunction "7_7") (pintype "passive"))
    )
    (net (code "94") (name "unconnected-(CON18-Pad8)") (class "Default")
      (node (ref "CON18") (pin "8") (pinfunction "8_8") (pintype "passive"))
    )
    (net (code "95") (name "unconnected-(CON18-Pad9)") (class "Default")
      (node (ref "CON18") (pin "9") (pinfunction "9_9") (pintype "passive"))
    )
    (net (code "96") (name "unconnected-(CON18-Pad10)") (class "Default")
      (node (ref "CON18") (pin "10") (pinfunction "10_10") (pintype "passive"))
    )
    (net (code "97") (name "unconnected-(CON18-Pad11)") (class "Default")
      (node (ref "CON18") (pin "11") (pinfunction "11_11") (pintype "passive"))
    )
    (net (code "98") (name "unconnected-(CON18-Pad12)") (class "Default")
      (node (ref "CON18") (pin "12") (pinfunction "12_12") (pintype "passive"))
    )
    (net (code "99") (name "unconnected-(CON18-Pad13)") (class "Default")
      (node (ref "CON18") (pin "13") (pinfunction "13_13") (pintype "passive"))
    )
    (net (code "100") (name "unconnected-(CON18-Pad14)") (class "Default")
      (node (ref "CON18") (pin "14") (pinfunction "14_14") (pintype "passive"))
    )
    (net (code "101") (name "unconnected-(CON18-Pad15)") (class "Default")
      (node (ref "CON18") (pin "15") (pinfunction "15_15") (pintype "passive"))
    )
    (net (code "102") (name "unconnected-(CON18-Pad16)") (class "Default")
      (node (ref "CON18") (pin "16") (pinfunction "16_16") (pintype "passive"))
    )
    (net (code "103") (name "unconnected-(CON18-Pad17)") (class "Default")
      (node (ref "CON18") (pin "17") (pinfunction "17_17") (pintype "passive"))
    )
    (net (code "104") (name "unconnected-(CON18-Pad18)") (class "Default")
      (node (ref "CON18") (pin "18") (pinfunction "18_18") (pintype "passive"))
    )
    (net (code "105") (name "unconnected-(CON18-Pad19)") (class "Default")
      (node (ref "CON18") (pin "19") (pinfunction "19_19") (pintype "passive"))
    )
    (net (code "106") (name "unconnected-(CON18-Pad20)") (class "Default")
      (node (ref "CON18") (pin "20") (pinfunction "20_20") (pintype "passive"))
    )
    (net (code "107") (name "unconnected-(CON18-Pad21)") (class "Default")
      (node (ref "CON18") (pin "21") (pinfunction "21_21") (pintype "passive"))
    )
    (net (code "108") (name "unconnected-(CON18-Pad22)") (class "Default")
      (node (ref "CON18") (pin "22") (pinfunction "22_22") (pintype "passive"))
    )
    (net (code "109") (name "unconnected-(CON18-Pad23)") (class "Default")
      (node (ref "CON18") (pin "23") (pinfunction "23_23") (pintype "passive"))
    )
    (net (code "110") (name "unconnected-(CON18-Pad24)") (class "Default")
      (node (ref "CON18") (pin "24") (pinfunction "24_24") (pintype "passive"))
    )
    (net (code "111") (name "unconnected-(CON18-Pad26)") (class "Default")
      (node (ref "CON18") (pin "26") (pinfunction "26_26") (pintype "passive"))
    )
    (net (code "112") (name "unconnected-(CON18-Pad28)") (class "Default")
      (node (ref "CON18") (pin "28") (pinfunction "28_28") (pintype "passive"))
    )
    (net (code "113") (name "unconnected-(CON18-Pad29)") (class "Default")
      (node (ref "CON18") (pin "29") (pinfunction "29_29") (pintype "passive"))
    )
    (net (code "114") (name "unconnected-(CON18-Pad30)") (class "Default")
      (node (ref "CON18") (pin "30") (pinfunction "30_30") (pintype "passive"))
    )
    (net (code "115") (name "unconnected-(CON19-Pad1)") (class "Default")
      (node (ref "CON19") (pin "1") (pinfunction "1_1") (pintype "passive"))
    )
    (net (code "116") (name "unconnected-(CON19-Pad2)") (class "Default")
      (node (ref "CON19") (pin "2") (pinfunction "2_2") (pintype "passive"))
    )
    (net (code "117") (name "unconnected-(CON19-Pad3)") (class "Default")
      (node (ref "CON19") (pin "3") (pinfunction "3_3") (pintype "passive"))
    )
    (net (code "118") (name "unconnected-(CON19-Pad4)") (class "Default")
      (node (ref "CON19") (pin "4") (pinfunction "4_4") (pintype "passive"))
    )
    (net (code "119") (name "unconnected-(CON19-Pad5)") (class "Default")
      (node (ref "CON19") (pin "5") (pinfunction "5_5") (pintype "passive"))
    )
    (net (code "120") (name "unconnected-(CON19-Pad6)") (class "Default")
      (node (ref "CON19") (pin "6") (pinfunction "6_6") (pintype "passive"))
    )
    (net (code "121") (name "unconnected-(CON19-Pad8)") (class "Default")
      (node (ref "CON19") (pin "8") (pinfunction "8_8") (pintype "passive"))
    )
    (net (code "122") (name "unconnected-(CON19-Pad10)") (class "Default")
      (node (ref "CON19") (pin "10") (pinfunction "10_10") (pintype "passive"))
    )
    (net (code "123") (name "unconnected-(CON19-Pad12)") (class "Default")
      (node (ref "CON19") (pin "12") (pinfunction "12_12") (pintype "passive"))
    )
    (net (code "124") (name "unconnected-(CON19-Pad14)") (class "Default")
      (node (ref "CON19") (pin "14") (pinfunction "14_14") (pintype "passive"))
    )
    (net (code "125") (name "unconnected-(CON19-Pad15)") (class "Default")
      (node (ref "CON19") (pin "15") (pinfunction "15_15") (pintype "passive"))
    )
    (net (code "126") (name "unconnected-(CON19-Pad16)") (class "Default")
      (node (ref "CON19") (pin "16") (pinfunction "16_16") (pintype "passive"))
    )
    (net (code "127") (name "unconnected-(CON20-Pad2)") (class "Default")
      (node (ref "CON20") (pin "2") (pinfunction "2_2") (pintype "passive"))
    )
    (net (code "128") (name "unconnected-(CON20-Pad4)") (class "Default")
      (node (ref "CON20") (pin "4") (pinfunction "4_4") (pintype "passive"))
    )
    (net (code "129") (name "unconnected-(CON20-Pad6)") (class "Default")
      (node (ref "CON20") (pin "6") (pinfunction "6_6") (pintype "passive"))
    )
    (net (code "130") (name "unconnected-(CON20-Pad8)") (class "Default")
      (node (ref "CON20") (pin "8") (pinfunction "8_8") (pintype "passive"))
    )
    (net (code "131") (name "unconnected-(CON20-Pad9)") (class "Default")
      (node (ref "CON20") (pin "9") (pinfunction "9_9") (pintype "passive"))
    )
    (net (code "132") (name "unconnected-(CON20-Pad10)") (class "Default")
      (node (ref "CON20") (pin "10") (pinfunction "10_10") (pintype "passive"))
    )
    (net (code "133") (name "unconnected-(CON20-Pad11)") (class "Default")
      (node (ref "CON20") (pin "11") (pinfunction "11_11") (pintype "passive"))
    )
    (net (code "134") (name "unconnected-(CON20-Pad12)") (class "Default")
      (node (ref "CON20") (pin "12") (pinfunction "12_12") (pintype "passive"))
    )
    (net (code "135") (name "unconnected-(CON20-Pad13)") (class "Default")
      (node (ref "CON20") (pin "13") (pinfunction "13_13") (pintype "passive"))
    )
    (net (code "136") (name "unconnected-(CON20-Pad14)") (class "Default")
      (node (ref "CON20") (pin "14") (pinfunction "14_14") (pintype "passive"))
    )
    (net (code "137") (name "unconnected-(CON20-Pad15)") (class "Default")
      (node (ref "CON20") (pin "15") (pinfunction "15_15") (pintype "passive"))
    )
    (net (code "138") (name "unconnected-(CON20-Pad16)") (class "Default")
      (node (ref "CON20") (pin "16") (pinfunction "16_16") (pintype "passive"))
    )
    (net (code "139") (name "unconnected-(CON20-Pad17)") (class "Default")
      (node (ref "CON20") (pin "17") (pinfunction "17_17") (pintype "passive"))
    )
    (net (code "140") (name "unconnected-(CON20-Pad18)") (class "Default")
      (node (ref "CON20") (pin "18") (pinfunction "18_18") (pintype "passive"))
    )
    (net (code "141") (name "unconnected-(CON20-Pad19)") (class "Default")
      (node (ref "CON20") (pin "19") (pinfunction "19_19") (pintype "passive"))
    )
    (net (code "142") (name "unconnected-(CON20-Pad20)") (class "Default")
      (node (ref "CON20") (pin "20") (pinfunction "20_20") (pintype "passive"))
    )
    (net (code "143") (name "unconnected-(IC1-PWRGD-Pad6)") (class "Default")
      (node (ref "IC1") (pin "6") (pinfunction "PWRGD_6") (pintype "bidirectional"))
    )
    (net (code "144") (name "unconnected-(IC2-STBY-Pad8)") (class "Default")
      (node (ref "IC2") (pin "8") (pinfunction "STBY_8") (pintype "bidirectional"))
    )
    (net (code "145") (name "unconnected-(IC6-STBY-Pad8)") (class "Default")
      (node (ref "IC6") (pin "8") (pinfunction "STBY_8") (pintype "bidirectional"))
    )
  )
)
